# Zio_Qwiic_HAT.net
KiCad netlist of a schematic drawn in EAGLE
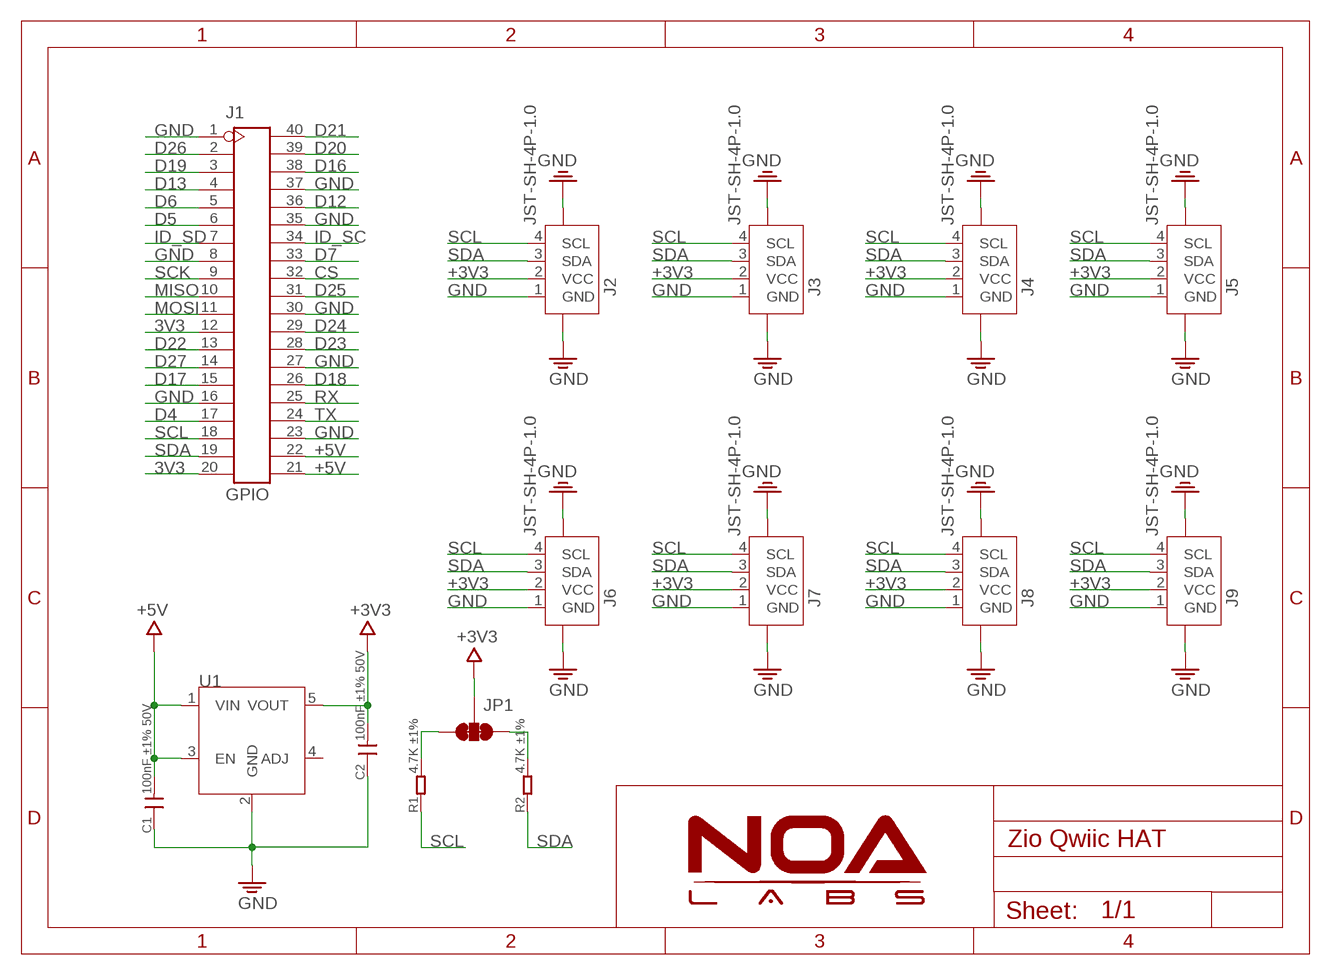
[diagram p0: schematic, sheet 1]

(export (version "E")
  (design (tool "Eeschema 10.0.6"))
  (components
    (comp (ref "C1")
      (value "100nF ±1% 50V")
      (footprint "eagle-import:C0603")
      (libsource (lib "eagle-import") (part "C-0603"))
    )
    (comp (ref "C2")
      (value "100nF ±1% 50V")
      (footprint "eagle-import:C0603")
      (libsource (lib "eagle-import") (part "C-0603"))
    )
    (comp (ref "J1")
      (value "GPIO")
      (footprint "eagle-import:2X20P_2.54")
      (libsource (lib "eagle-import") (part "HEADER_2X20P"))
    )
    (comp (ref "J2")
      (value "JST-SH-4P-1.0")
      (footprint "eagle-import:JST-SH-4P")
      (libsource (lib "eagle-import") (part "JST-SH-4P-1.0"))
    )
    (comp (ref "J3")
      (value "JST-SH-4P-1.0")
      (footprint "eagle-import:JST-SH-4P")
      (libsource (lib "eagle-import") (part "JST-SH-4P-1.0"))
    )
    (comp (ref "J4")
      (value "JST-SH-4P-1.0")
      (footprint "eagle-import:JST-SH-4P")
      (libsource (lib "eagle-import") (part "JST-SH-4P-1.0"))
    )
    (comp (ref "J5")
      (value "JST-SH-4P-1.0")
      (footprint "eagle-import:JST-SH-4P")
      (libsource (lib "eagle-import") (part "JST-SH-4P-1.0"))
    )
    (comp (ref "J6")
      (value "JST-SH-4P-1.0")
      (footprint "eagle-import:JST-SH-4P")
      (libsource (lib "eagle-import") (part "JST-SH-4P-1.0"))
    )
    (comp (ref "J7")
      (value "JST-SH-4P-1.0")
      (footprint "eagle-import:JST-SH-4P")
      (libsource (lib "eagle-import") (part "JST-SH-4P-1.0"))
    )
    (comp (ref "J8")
      (value "JST-SH-4P-1.0")
      (footprint "eagle-import:JST-SH-4P")
      (libsource (lib "eagle-import") (part "JST-SH-4P-1.0"))
    )
    (comp (ref "J9")
      (value "JST-SH-4P-1.0")
      (footprint "eagle-import:JST-SH-4P")
      (libsource (lib "eagle-import") (part "JST-SH-4P-1.0"))
    )
    (comp (ref "JP1")
      (value "SMT-JUMPER_3_2-NC_TRACE")
      (footprint "eagle-import:SMT-JUMPER_3_2-NC_TRACE")
      (libsource (lib "eagle-import") (part "SMT-JUMPER_3_2-NC_TRACE"))
    )
    (comp (ref "R1")
      (value "4.7K ±1%")
      (footprint "eagle-import:R0603")
      (libsource (lib "eagle-import") (part "R-0603"))
    )
    (comp (ref "R2")
      (value "4.7K ±1%")
      (footprint "eagle-import:R0603")
      (libsource (lib "eagle-import") (part "R-0603"))
    )
    (comp (ref "U1")
      (value "AP2112")
      (footprint "eagle-import:SOT23-5")
      (libsource (lib "eagle-import") (part "AP2112"))
    )
  )
  (nets
    (net (code "1") (name "+3V3") (class "Default")
      (node (ref "C2") (pin "2") (pinfunction "2_2") (pintype "passive"))
      (node (ref "J2") (pin "2") (pinfunction "VCC_2") (pintype "bidirectional"))
      (node (ref "J3") (pin "2") (pinfunction "VCC_2") (pintype "bidirectional"))
      (node (ref "J4") (pin "2") (pinfunction "VCC_2") (pintype "bidirectional"))
      (node (ref "J5") (pin "2") (pinfunction "VCC_2") (pintype "bidirectional"))
      (node (ref "J6") (pin "2") (pinfunction "VCC_2") (pintype "bidirectional"))
      (node (ref "J7") (pin "2") (pinfunction "VCC_2") (pintype "bidirectional"))
      (node (ref "J8") (pin "2") (pinfunction "VCC_2") (pintype "bidirectional"))
      (node (ref "J9") (pin "2") (pinfunction "VCC_2") (pintype "bidirectional"))
      (node (ref "JP1") (pin "2") (pinfunction "2_2") (pintype "passive"))
      (node (ref "U1") (pin "5") (pinfunction "VOUT_5") (pintype "bidirectional"))
    )
    (net (code "2") (name "+5V") (class "Default")
      (node (ref "C1") (pin "2") (pinfunction "2_2") (pintype "passive"))
      (node (ref "J1") (pin "21") (pinfunction "21_21") (pintype "bidirectional"))
      (node (ref "J1") (pin "22") (pinfunction "22_22") (pintype "bidirectional"))
      (node (ref "U1") (pin "1") (pinfunction "VIN_1") (pintype "bidirectional"))
      (node (ref "U1") (pin "3") (pinfunction "EN_3") (pintype "bidirectional"))
    )
    (net (code "3") (name "/3V3") (class "Default")
      (node (ref "J1") (pin "12") (pinfunction "12_12") (pintype "bidirectional"))
      (node (ref "J1") (pin "20") (pinfunction "20_20") (pintype "bidirectional"))
    )
    (net (code "4") (name "/CS") (class "Default")
      (node (ref "J1") (pin "32") (pinfunction "32_32") (pintype "bidirectional"))
    )
    (net (code "5") (name "/D4") (class "Default")
      (node (ref "J1") (pin "17") (pinfunction "17_17") (pintype "bidirectional"))
    )
    (net (code "6") (name "/D5") (class "Default")
      (node (ref "J1") (pin "6") (pinfunction "6_6") (pintype "bidirectional"))
    )
    (net (code "7") (name "/D6") (class "Default")
      (node (ref "J1") (pin "5") (pinfunction "5_5") (pintype "bidirectional"))
    )
    (net (code "8") (name "/D7") (class "Default")
      (node (ref "J1") (pin "33") (pinfunction "33_33") (pintype "bidirectional"))
    )
    (net (code "9") (name "/D12") (class "Default")
      (node (ref "J1") (pin "36") (pinfunction "36_36") (pintype "bidirectional"))
    )
    (net (code "10") (name "/D13") (class "Default")
      (node (ref "J1") (pin "4") (pinfunction "4_4") (pintype "bidirectional"))
    )
    (net (code "11") (name "/D16") (class "Default")
      (node (ref "J1") (pin "38") (pinfunction "38_38") (pintype "bidirectional"))
    )
    (net (code "12") (name "/D17") (class "Default")
      (node (ref "J1") (pin "15") (pinfunction "15_15") (pintype "bidirectional"))
    )
    (net (code "13") (name "/D18") (class "Default")
      (node (ref "J1") (pin "26") (pinfunction "26_26") (pintype "bidirectional"))
    )
    (net (code "14") (name "/D19") (class "Default")
      (node (ref "J1") (pin "3") (pinfunction "3_3") (pintype "bidirectional"))
    )
    (net (code "15") (name "/D20") (class "Default")
      (node (ref "J1") (pin "39") (pinfunction "39_39") (pintype "bidirectional"))
    )
    (net (code "16") (name "/D21") (class "Default")
      (node (ref "J1") (pin "40") (pinfunction "40_40") (pintype "bidirectional"))
    )
    (net (code "17") (name "/D22") (class "Default")
      (node (ref "J1") (pin "13") (pinfunction "13_13") (pintype "bidirectional"))
    )
    (net (code "18") (name "/D23") (class "Default")
      (node (ref "J1") (pin "28") (pinfunction "28_28") (pintype "bidirectional"))
    )
    (net (code "19") (name "/D24") (class "Default")
      (node (ref "J1") (pin "29") (pinfunction "29_29") (pintype "bidirectional"))
    )
    (net (code "20") (name "/D25") (class "Default")
      (node (ref "J1") (pin "31") (pinfunction "31_31") (pintype "bidirectional"))
    )
    (net (code "21") (name "/D26") (class "Default")
      (node (ref "J1") (pin "2") (pinfunction "2_2") (pintype "bidirectional"))
    )
    (net (code "22") (name "/D27") (class "Default")
      (node (ref "J1") (pin "14") (pinfunction "14_14") (pintype "bidirectional"))
    )
    (net (code "23") (name "/ID_SC") (class "Default")
      (node (ref "J1") (pin "34") (pinfunction "34_34") (pintype "bidirectional"))
    )
    (net (code "24") (name "/ID_SD") (class "Default")
      (node (ref "J1") (pin "7") (pinfunction "7_7") (pintype "bidirectional"))
    )
    (net (code "25") (name "/MISO") (class "Default")
      (node (ref "J1") (pin "10") (pinfunction "10_10") (pintype "bidirectional"))
    )
    (net (code "26") (name "/MOSI") (class "Default")
      (node (ref "J1") (pin "11") (pinfunction "11_11") (pintype "bidirectional"))
    )
    (net (code "27") (name "/RX") (class "Default")
      (node (ref "J1") (pin "25") (pinfunction "25_25") (pintype "bidirectional"))
    )
    (net (code "28") (name "/SCK") (class "Default")
      (node (ref "J1") (pin "9") (pinfunction "9_9") (pintype "bidirectional"))
    )
    (net (code "29") (name "/SCL") (class "Default")
      (node (ref "J1") (pin "18") (pinfunction "18_18") (pintype "bidirectional"))
      (node (ref "J2") (pin "4") (pinfunction "SCL_4") (pintype "bidirectional"))
      (node (ref "J3") (pin "4") (pinfunction "SCL_4") (pintype "bidirectional"))
      (node (ref "J4") (pin "4") (pinfunction "SCL_4") (pintype "bidirectional"))
      (node (ref "J5") (pin "4") (pinfunction "SCL_4") (pintype "bidirectional"))
      (node (ref "J6") (pin "4") (pinfunction "SCL_4") (pintype "bidirectional"))
      (node (ref "J7") (pin "4") (pinfunction "SCL_4") (pintype "bidirectional"))
      (node (ref "J8") (pin "4") (pinfunction "SCL_4") (pintype "bidirectional"))
      (node (ref "J9") (pin "4") (pinfunction "SCL_4") (pintype "bidirectional"))
      (node (ref "R1") (pin "1") (pinfunction "1_1") (pintype "passive"))
    )
    (net (code "30") (name "/SDA") (class "Default")
      (node (ref "J1") (pin "19") (pinfunction "19_19") (pintype "bidirectional"))
      (node (ref "J2") (pin "3") (pinfunction "SDA_3") (pintype "bidirectional"))
      (node (ref "J3") (pin "3") (pinfunction "SDA_3") (pintype "bidirectional"))
      (node (ref "J4") (pin "3") (pinfunction "SDA_3") (pintype "bidirectional"))
      (node (ref "J5") (pin "3") (pinfunction "SDA_3") (pintype "bidirectional"))
      (node (ref "J6") (pin "3") (pinfunction "SDA_3") (pintype "bidirectional"))
      (node (ref "J7") (pin "3") (pinfunction "SDA_3") (pintype "bidirectional"))
      (node (ref "J8") (pin "3") (pinfunction "SDA_3") (pintype "bidirectional"))
      (node (ref "J9") (pin "3") (pinfunction "SDA_3") (pintype "bidirectional"))
      (node (ref "R2") (pin "1") (pinfunction "1_1") (pintype "passive"))
    )
    (net (code "31") (name "/TX") (class "Default")
      (node (ref "J1") (pin "24") (pinfunction "24_24") (pintype "bidirectional"))
    )
    (net (code "32") (name "GND") (class "Default")
      (node (ref "C1") (pin "1") (pinfunction "1_1") (pintype "passive"))
      (node (ref "C2") (pin "1") (pinfunction "1_1") (pintype "passive"))
      (node (ref "J1") (pin "1") (pinfunction "1_1") (pintype "bidirectional"))
      (node (ref "J1") (pin "16") (pinfunction "16_16") (pintype "bidirectional"))
      (node (ref "J1") (pin "23") (pinfunction "23_23") (pintype "bidirectional"))
      (node (ref "J1") (pin "27") (pinfunction "27_27") (pintype "bidirectional"))
      (node (ref "J1") (pin "30") (pinfunction "30_30") (pintype "bidirectional"))
      (node (ref "J1") (pin "35") (pinfunction "35_35") (pintype "bidirectional"))
      (node (ref "J1") (pin "37") (pinfunction "37_37") (pintype "bidirectional"))
      (node (ref "J1") (pin "8") (pinfunction "8_8") (pintype "bidirectional"))
      (node (ref "J2") (pin "1") (pinfunction "GND_1") (pintype "bidirectional"))
      (node (ref "J2") (pin "NC1") (pinfunction "5_NC1") (pintype "bidirectional"))
      (node (ref "J2") (pin "NC2") (pinfunction "6_NC2") (pintype "bidirectional"))
      (node (ref "J3") (pin "1") (pinfunction "GND_1") (pintype "bidirectional"))
      (node (ref "J3") (pin "NC1") (pinfunction "5_NC1") (pintype "bidirectional"))
      (node (ref "J3") (pin "NC2") (pinfunction "6_NC2") (pintype "bidirectional"))
      (node (ref "J4") (pin "1") (pinfunction "GND_1") (pintype "bidirectional"))
      (node (ref "J4") (pin "NC1") (pinfunction "5_NC1") (pintype "bidirectional"))
      (node (ref "J4") (pin "NC2") (pinfunction "6_NC2") (pintype "bidirectional"))
      (node (ref "J5") (pin "1") (pinfunction "GND_1") (pintype "bidirectional"))
      (node (ref "J5") (pin "NC1") (pinfunction "5_NC1") (pintype "bidirectional"))
      (node (ref "J5") (pin "NC2") (pinfunction "6_NC2") (pintype "bidirectional"))
      (node (ref "J6") (pin "1") (pinfunction "GND_1") (pintype "bidirectional"))
      (node (ref "J6") (pin "NC1") (pinfunction "5_NC1") (pintype "bidirectional"))
      (node (ref "J6") (pin "NC2") (pinfunction "6_NC2") (pintype "bidirectional"))
      (node (ref "J7") (pin "1") (pinfunction "GND_1") (pintype "bidirectional"))
      (node (ref "J7") (pin "NC1") (pinfunction "5_NC1") (pintype "bidirectional"))
      (node (ref "J7") (pin "NC2") (pinfunction "6_NC2") (pintype "bidirectional"))
      (node (ref "J8") (pin "1") (pinfunction "GND_1") (pintype "bidirectional"))
      (node (ref "J8") (pin "NC1") (pinfunction "5_NC1") (pintype "bidirectional"))
      (node (ref "J8") (pin "NC2") (pinfunction "6_NC2") (pintype "bidirectional"))
      (node (ref "J9") (pin "1") (pinfunction "GND_1") (pintype "bidirectional"))
      (node (ref "J9") (pin "NC1") (pinfunction "5_NC1") (pintype "bidirectional"))
      (node (ref "J9") (pin "NC2") (pinfunction "6_NC2") (pintype "bidirectional"))
      (node (ref "U1") (pin "2") (pinfunction "GND_2") (pintype "bidirectional"))
    )
    (net (code "33") (name "Net-(JP1-Pad1)") (class "Default")
      (node (ref "JP1") (pin "1") (pinfunction "1_1") (pintype "passive"))
      (node (ref "R2") (pin "2") (pinfunction "2_2") (pintype "passive"))
    )
    (net (code "34") (name "Net-(JP1-Pad3)") (class "Default")
      (node (ref "JP1") (pin "3") (pinfunction "3_3") (pintype "passive"))
      (node (ref "R1") (pin "2") (pinfunction "2_2") (pintype "passive"))
    )
    (net (code "35") (name "unconnected-(U1-ADJ-Pad4)") (class "Default")
      (node (ref "U1") (pin "4") (pinfunction "ADJ_4") (pintype "bidirectional"))
    )
  )
)
